# SENSOR.net
KiCad netlist of a schematic drawn in Altium Designer
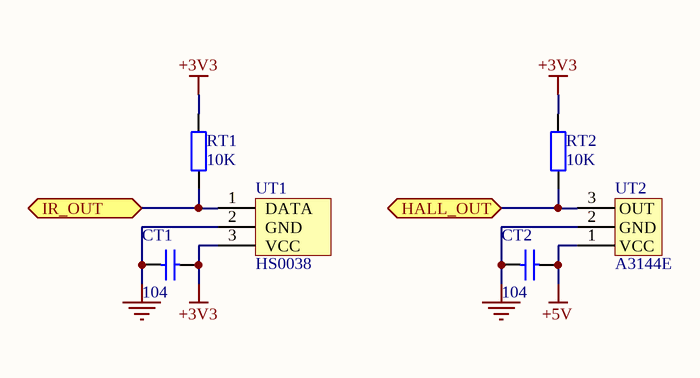
[diagram p0: SENSOR.SchDoc]

(export (version "E")
  (design (tool "Eeschema 10.0.6"))
  (components
    (comp (ref "CT1")
      (value "104")
      (footprint "CAPC1608N")
      (description "Capacitor")
      (fields (field (name "Comment") "Cap1") (field (name "PUBLISHER") "Altium Limited"))
      (libsource (lib "Peace的集成库") (part "Cap1"))
    )
    (comp (ref "CT2")
      (value "104")
      (footprint "CAPC1608N")
      (description "Capacitor")
      (fields (field (name "Comment") "Cap1") (field (name "PUBLISHER") "Altium Limited"))
      (libsource (lib "Peace的集成库") (part "Cap1"))
    )
    (comp (ref "RT1")
      (value "10K")
      (footprint "RESC1608N")
      (description "Resistor")
      (fields (field (name "Comment") "Res1") (field (name "PUBLISHER") "Altium Limited"))
      (libsource (lib "Peace的集成库") (part "Res1"))
    )
    (comp (ref "RT2")
      (value "10K")
      (footprint "RESC1608N")
      (description "Resistor")
      (fields (field (name "Comment") "Res1") (field (name "PUBLISHER") "Altium Limited"))
      (libsource (lib "Peace的集成库") (part "Res1"))
    )
    (comp (ref "UT1") (value "HS0038") (footprint "HS0038") (libsource (lib "原理图库") (part "HS0038")))
    (comp (ref "UT2") (value "A3144E") (footprint "A3144E") (libsource (lib "原理图库") (part "A3144E")))
  )
  (nets
    (net (code "1") (name "+3V3") (class "Default")
      (node (ref "CT1") (pin "1") (pinfunction "1_1") (pintype "passive"))
      (node (ref "RT1") (pin "1") (pinfunction "1_1") (pintype "passive"))
      (node (ref "RT2") (pin "1") (pinfunction "1_1") (pintype "passive"))
      (node (ref "UT1") (pin "3") (pinfunction "VCC_3") (pintype "passive"))
    )
    (net (code "2") (name "+5V") (class "Default")
      (node (ref "CT2") (pin "1") (pinfunction "1_1") (pintype "passive"))
      (node (ref "UT2") (pin "1") (pinfunction "VCC_1") (pintype "passive"))
    )
    (net (code "3") (name "/HALL_OUT") (class "Default")
      (node (ref "RT2") (pin "2") (pinfunction "2_2") (pintype "passive"))
      (node (ref "UT2") (pin "3") (pinfunction "OUT_3") (pintype "passive"))
    )
    (net (code "4") (name "/IR_OUT") (class "Default")
      (node (ref "RT1") (pin "2") (pinfunction "2_2") (pintype "passive"))
      (node (ref "UT1") (pin "1") (pinfunction "DATA_1") (pintype "passive"))
    )
    (net (code "5") (name "GND") (class "Default")
      (node (ref "CT1") (pin "2") (pinfunction "2_2") (pintype "passive"))
      (node (ref "CT2") (pin "2") (pinfunction "2_2") (pintype "passive"))
      (node (ref "UT1") (pin "2") (pinfunction "GND_2") (pintype "passive"))
      (node (ref "UT2") (pin "2") (pinfunction "GND_2") (pintype "passive"))
    )
  )
)
